# 11_-_EEPROM.net
KiCad netlist of a schematic drawn in Altium Designer
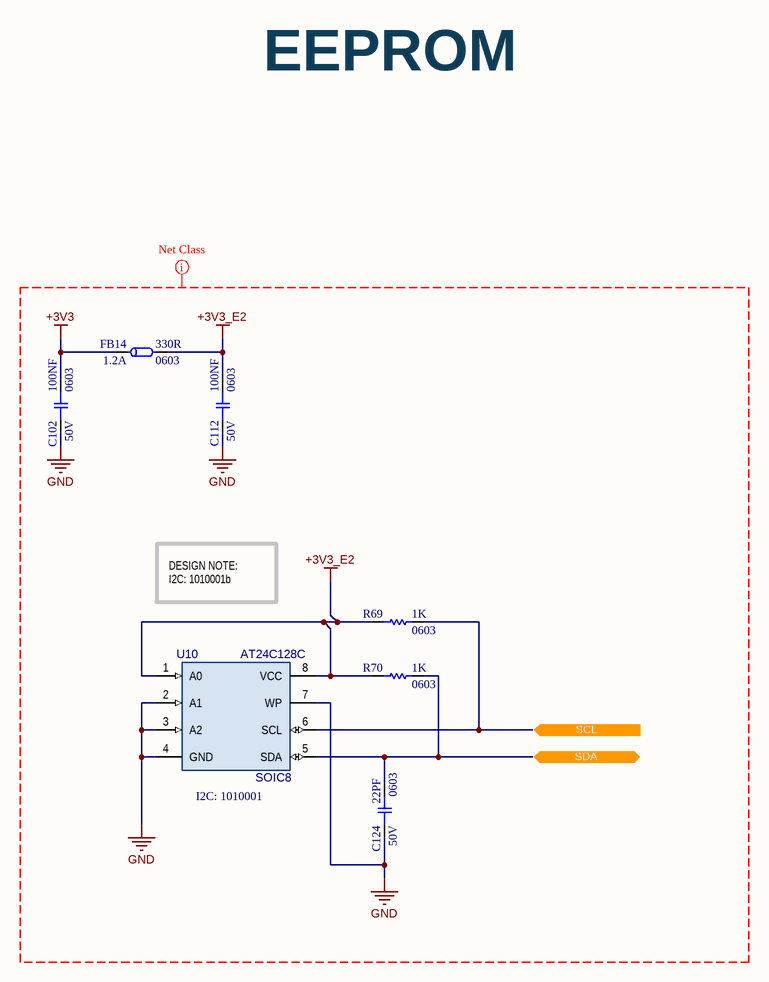
[diagram p0: [11] - EEPROM.SchDoc]

(export (version "E")
  (design (tool "Eeschema 10.0.6"))
  (components
    (comp (ref "C102")
      (value "100NF")
      (footprint "C-0603")
      (description "CAP CER 0.1UF 50V X7R 0603")
      (fields
        (field (name "MANUFACTURER") "TDK")
        (field (name "MANUFACTURER PART NUMBER") "C1608X7R1H104K080AA")
        (field (name "VOLTAGE RATING") "50V")
        (field (name "CASE/PACKAGE") "0603")
        (field (name ".CREATOR") "F:TALI")
      )
      (libsource (lib "BARKO_SCHLIB") (part "C-100NF-0603"))
    )
    (comp (ref "C112")
      (value "100NF")
      (footprint "C-0603")
      (description "CAP CER 0.1UF 50V X7R 0603")
      (fields
        (field (name "MANUFACTURER") "TDK")
        (field (name "MANUFACTURER PART NUMBER") "C1608X7R1H104K080AA")
        (field (name "VOLTAGE RATING") "50V")
        (field (name "CASE/PACKAGE") "0603")
        (field (name ".CREATOR") "F:TALI")
      )
      (libsource (lib "BARKO_SCHLIB") (part "C-100NF-0603"))
    )
    (comp (ref "C124")
      (value "22PF")
      (footprint "C-0603")
      (description "CAP CER 22PF 50V C0G/NP0 0603")
      (fields
        (field (name "MANUFACTURER") "Samsung")
        (field (name "MANUFACTURER PART NUMBER") "CL10C220JB8NNNC")
        (field (name "VOLTAGE RATING") "50V")
        (field (name "CASE/PACKAGE") "0603")
        (field (name ".CREATOR") "F:TALI")
      )
      (libsource (lib "BARKO_SCHLIB") (part "C-22PF-0603"))
    )
    (comp (ref "FB14")
      (value "330R")
      (footprint "FB-0603")
      (description "FERRITE BEAD 330 OHM 0603 1LN")
      (fields
        (field (name "MANUFACTURER") "Murata")
        (field (name "MANUFACTURER PART NUMBER") "BLM18PG331SN1D")
        (field (name "CASE/PACKAGE") "0603")
        (field (name "DC CURRENT") "1.2A")
      )
      (libsource (lib "BARKO_SCHLIB") (part "FB-330R-0603"))
    )
    (comp (ref "R69")
      (value "1K")
      (footprint "R-0603")
      (description "RES SMD 1K OHM 5% 1/10W 0603")
      (fields
        (field (name "MANUFACTURER") "Yageo")
        (field (name "MANUFACTURER PART NUMBER") "RC0603JR-071KL")
        (field (name "CASE CODE (IMPERIAL)") "0603")
      )
      (libsource (lib "BARKO_SCHLIB") (part "R-1K-0603"))
    )
    (comp (ref "R70")
      (value "1K")
      (footprint "R-0603")
      (description "RES SMD 1K OHM 5% 1/10W 0603")
      (fields
        (field (name "MANUFACTURER") "Yageo")
        (field (name "MANUFACTURER PART NUMBER") "RC0603JR-071KL")
        (field (name "CASE CODE (IMPERIAL)") "0603")
      )
      (libsource (lib "BARKO_SCHLIB") (part "R-1K-0603"))
    )
    (comp (ref "U10")
      (value "AT24C128C")
      (footprint "SOIC8")
      (description "IC EEPROM 128K I2C 1MHZ 8SOIC")
      (fields
        (field (name "MANUFACTURER") "Microchip / Atmel")
        (field (name "MANUFACTURER PART NUMBER") "AT24C128C-SSHM-B")
        (field (name "CASE/PACKAGE") "SOIC8")
      )
      (libsource (lib "BARKO_SCHLIB") (part "IC-AT24C128C-SSHM-B"))
    )
  )
  (nets
    (net (code "1") (name "+3V3") (class "Default")
      (node (ref "C102") (pin "2") (pinfunction "2_2") (pintype "passive"))
      (node (ref "FB14") (pin "1") (pinfunction "1_1") (pintype "passive"))
    )
    (net (code "2") (name "+3V3_E2") (class "Default")
      (node (ref "C112") (pin "2") (pinfunction "2_2") (pintype "passive"))
      (node (ref "FB14") (pin "2") (pinfunction "2_2") (pintype "passive"))
      (node (ref "R69") (pin "1") (pinfunction "1_1") (pintype "passive"))
      (node (ref "R70") (pin "1") (pinfunction "1_1") (pintype "passive"))
      (node (ref "U10") (pin "1") (pinfunction "A0_1") (pintype "input"))
      (node (ref "U10") (pin "8") (pinfunction "VCC_8") (pintype "power_in"))
    )
    (net (code "3") (name "/SCL") (class "Default")
      (node (ref "R69") (pin "2") (pinfunction "2_2") (pintype "passive"))
      (node (ref "U10") (pin "6") (pinfunction "SCL_6") (pintype "bidirectional"))
    )
    (net (code "4") (name "/SDA") (class "Default")
      (node (ref "C124") (pin "2") (pinfunction "2_2") (pintype "passive"))
      (node (ref "R70") (pin "2") (pinfunction "2_2") (pintype "passive"))
      (node (ref "U10") (pin "5") (pinfunction "SDA_5") (pintype "bidirectional"))
    )
    (net (code "5") (name "GND") (class "Default")
      (node (ref "C102") (pin "1") (pinfunction "1_1") (pintype "passive"))
      (node (ref "C112") (pin "1") (pinfunction "1_1") (pintype "passive"))
      (node (ref "C124") (pin "1") (pinfunction "1_1") (pintype "passive"))
      (node (ref "U10") (pin "2") (pinfunction "A1_2") (pintype "input"))
      (node (ref "U10") (pin "3") (pinfunction "A2_3") (pintype "input"))
      (node (ref "U10") (pin "4") (pinfunction "GND_4") (pintype "power_in"))
      (node (ref "U10") (pin "7") (pinfunction "WP_7") (pintype "passive"))
    )
  )
)
